# Analog_Input.net
KiCad netlist of a schematic drawn in Altium Designer
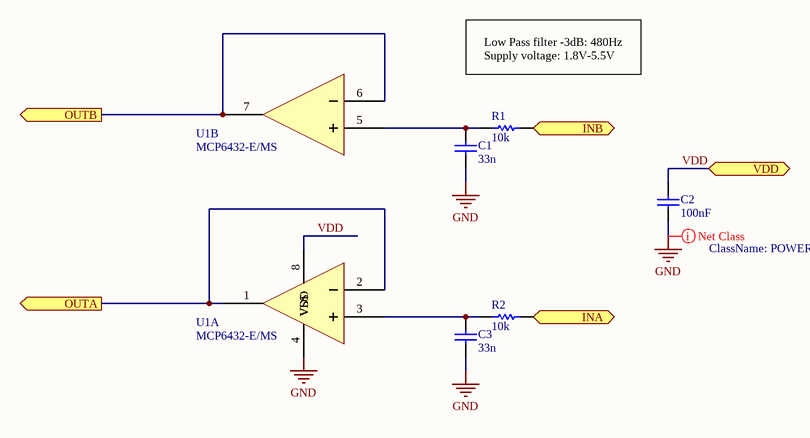
[diagram p0: Analog Input.SchDoc]

(export (version "E")
  (design (tool "Eeschema 10.0.6"))
  (components
    (comp (ref "C1")
      (value "33n")
      (footprint "agh_racing_2018:CAP_0603_IPC_HD")
      (description "Capacitor")
      (fields (field (name "Comment") "Cap"))
      (libsource (lib "agh_racing_2018") (part "Cap"))
    )
    (comp (ref "C2")
      (value "100nF")
      (footprint "agh_racing_2018:CAP_0603_IPC_HD")
      (description "Capacitor")
      (fields (field (name "Comment") "Cap"))
      (libsource (lib "agh_racing_2018") (part "Cap"))
    )
    (comp (ref "C3")
      (value "33n")
      (footprint "agh_racing_2018:CAP_0603_IPC_HD")
      (description "Capacitor")
      (fields (field (name "Comment") "Cap"))
      (libsource (lib "agh_racing_2018") (part "Cap"))
    )
    (comp (ref "R1")
      (value "10k")
      (footprint "agh_racing_2018:RES_0603_IPC_HD")
      (description "Resistor")
      (fields (field (name "Comment") "Res"))
      (libsource (lib "agh_racing_2018") (part "Res"))
    )
    (comp (ref "R2")
      (value "10k")
      (footprint "agh_racing_2018:RES_0603_IPC_HD")
      (description "Resistor")
      (fields (field (name "Comment") "Res"))
      (libsource (lib "agh_racing_2018") (part "Res"))
    )
    (comp (ref "U1")
      (value "MCP6432-E/MS")
      (footprint "agh_racing_2018:MSOP8_IPC_MD")
      (libsource (lib "agh_racing_2018") (part "MCP6432-E/MS"))
    )
  )
  (nets
    (net (code "1") (name "/INA") (class "Default")
      (node (ref "R2") (pin "2") (pinfunction "2_2") (pintype "passive"))
    )
    (net (code "2") (name "/INB") (class "Default")
      (node (ref "R1") (pin "2") (pinfunction "2_2") (pintype "passive"))
    )
    (net (code "3") (name "/OUTA") (class "Default")
      (node (ref "U1") (pin "1") (pinfunction "VOUTA_1") (pintype "passive"))
      (node (ref "U1") (pin "2") (pinfunction "VINA-_2") (pintype "passive"))
    )
    (net (code "4") (name "/OUTB") (class "Default")
      (node (ref "U1") (pin "6") (pinfunction "VINB-_6") (pintype "passive"))
      (node (ref "U1") (pin "7") (pinfunction "VOUTB_7") (pintype "passive"))
    )
    (net (code "5") (name "/VDD") (class "Default")
      (node (ref "C2") (pin "2") (pinfunction "2_2") (pintype "passive"))
      (node (ref "U1") (pin "8") (pinfunction "VDD_8") (pintype "power_in"))
    )
    (net (code "6") (name "GND") (class "Default")
      (node (ref "C1") (pin "1") (pinfunction "1_1") (pintype "passive"))
      (node (ref "C2") (pin "1") (pinfunction "1_1") (pintype "passive"))
      (node (ref "C3") (pin "1") (pinfunction "1_1") (pintype "passive"))
      (node (ref "U1") (pin "4") (pinfunction "VSS_4") (pintype "power_in"))
    )
    (net (code "7") (name "Net-(U1A-VINA+)") (class "Default")
      (node (ref "C3") (pin "2") (pinfunction "2_2") (pintype "passive"))
      (node (ref "R2") (pin "1") (pinfunction "1_1") (pintype "passive"))
      (node (ref "U1") (pin "3") (pinfunction "VINA+_3") (pintype "passive"))
    )
    (net (code "8") (name "Net-(U1B-VINB+)") (class "Default")
      (node (ref "C1") (pin "2") (pinfunction "2_2") (pintype "passive"))
      (node (ref "R1") (pin "1") (pinfunction "1_1") (pintype "passive"))
      (node (ref "U1") (pin "5") (pinfunction "VINB+_5") (pintype "passive"))
    )
  )
)
